# arduino_hc.net
KiCad netlist of a schematic drawn in EAGLE
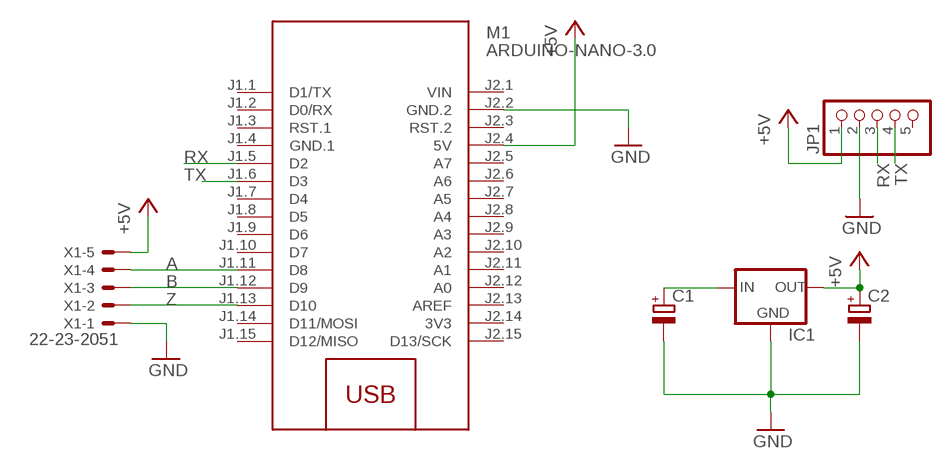
[diagram p0: schematic, sheet 1]

(export (version "E")
  (design (tool "Eeschema 10.0.6"))
  (components
    (comp (ref "C1")
      (value "CPOL-EUE2,5-6E")
      (footprint "eagle-import:E2,5-6E")
      (libsource (lib "eagle-import") (part "CPOL-EUE2,5-6E"))
    )
    (comp (ref "C2")
      (value "CPOL-EUE2,5-6E")
      (footprint "eagle-import:E2,5-6E")
      (libsource (lib "eagle-import") (part "CPOL-EUE2,5-6E"))
    )
    (comp (ref "IC1")
      (value "78XXS")
      (footprint "eagle-import:78XXS")
      (libsource (lib "eagle-import") (part "78XXS"))
    )
    (comp (ref "JP1")
      (value "PINHD-1X5")
      (footprint "eagle-import:1X05")
      (libsource (lib "eagle-import") (part "PINHD-1X5"))
    )
    (comp (ref "M1")
      (value "ARDUINO-NANO-3.0")
      (footprint "eagle-import:ARDUINO-NANO-3.0")
      (libsource (lib "eagle-import") (part "ARDUINO-NANO-3.0"))
    )
    (comp (ref "X1")
      (value "22-23-2051")
      (footprint "eagle-import:22-23-2051")
      (fields (field (name "MF") "MOLEX"))
      (libsource (lib "eagle-import") (part "22-23-2051"))
    )
  )
  (nets
    (net (code "1") (name "+5V") (class "Default")
      (node (ref "C2") (pin "+") (pinfunction "+_+") (pintype "passive"))
      (node (ref "IC1") (pin "OUT") (pinfunction "OUT_OUT") (pintype "passive"))
      (node (ref "JP1") (pin "1") (pinfunction "1_1") (pintype "passive"))
      (node (ref "M1") (pin "J2.4") (pinfunction "5V_J2.4") (pintype "power_in"))
      (node (ref "X1") (pin "5") (pinfunction "S_5") (pintype "passive"))
    )
    (net (code "2") (name "/3V3") (class "Default")
      (node (ref "M1") (pin "J2.14") (pinfunction "3V3_J2.14") (pintype "power_in"))
    )
    (net (code "3") (name "/A") (class "Default")
      (node (ref "M1") (pin "J1.11") (pinfunction "D8_J1.11") (pintype "bidirectional"))
      (node (ref "X1") (pin "4") (pinfunction "S_4") (pintype "passive"))
    )
    (net (code "4") (name "/B") (class "Default")
      (node (ref "M1") (pin "J1.12") (pinfunction "D9_J1.12") (pintype "bidirectional"))
      (node (ref "X1") (pin "3") (pinfunction "S_3") (pintype "passive"))
    )
    (net (code "5") (name "/GND.1") (class "Default")
      (node (ref "M1") (pin "J1.4") (pinfunction "GND.1_J1.4") (pintype "power_in"))
    )
    (net (code "6") (name "/RX") (class "Default")
      (node (ref "JP1") (pin "3") (pinfunction "3_3") (pintype "passive"))
      (node (ref "M1") (pin "J1.5") (pinfunction "D2_J1.5") (pintype "bidirectional"))
    )
    (net (code "7") (name "/TX") (class "Default")
      (node (ref "JP1") (pin "4") (pinfunction "4_4") (pintype "passive"))
      (node (ref "M1") (pin "J1.6") (pinfunction "D3_J1.6") (pintype "bidirectional"))
    )
    (net (code "8") (name "/VIN") (class "Default")
      (node (ref "M1") (pin "J2.1") (pinfunction "VIN_J2.1") (pintype "power_in"))
    )
    (net (code "9") (name "/Z") (class "Default")
      (node (ref "M1") (pin "J1.13") (pinfunction "D10_J1.13") (pintype "bidirectional"))
      (node (ref "X1") (pin "2") (pinfunction "S_2") (pintype "passive"))
    )
    (net (code "10") (name "GND") (class "Default")
      (node (ref "C1") (pin "-") (pinfunction "-_-") (pintype "passive"))
      (node (ref "C2") (pin "-") (pinfunction "-_-") (pintype "passive"))
      (node (ref "IC1") (pin "GND") (pinfunction "GND_GND") (pintype "input"))
      (node (ref "JP1") (pin "2") (pinfunction "2_2") (pintype "passive"))
      (node (ref "M1") (pin "J2.2") (pinfunction "GND.2_J2.2") (pintype "power_in"))
      (node (ref "X1") (pin "1") (pinfunction "S_1") (pintype "passive"))
    )
    (net (code "11") (name "Net-(C1-Pad+)") (class "Default")
      (node (ref "C1") (pin "+") (pinfunction "+_+") (pintype "passive"))
      (node (ref "IC1") (pin "IN") (pinfunction "IN_IN") (pintype "input"))
    )
    (net (code "12") (name "unconnected-(JP1-Pad5)") (class "Default")
      (node (ref "JP1") (pin "5") (pinfunction "5_5") (pintype "passive"))
    )
    (net (code "13") (name "unconnected-(M1-A0-PadJ2.12)") (class "Default")
      (node (ref "M1") (pin "J2.12") (pinfunction "A0_J2.12") (pintype "bidirectional"))
    )
    (net (code "14") (name "unconnected-(M1-A1-PadJ2.11)") (class "Default")
      (node (ref "M1") (pin "J2.11") (pinfunction "A1_J2.11") (pintype "bidirectional"))
    )
    (net (code "15") (name "unconnected-(M1-A2-PadJ2.10)") (class "Default")
      (node (ref "M1") (pin "J2.10") (pinfunction "A2_J2.10") (pintype "bidirectional"))
    )
    (net (code "16") (name "unconnected-(M1-A3-PadJ2.9)") (class "Default")
      (node (ref "M1") (pin "J2.9") (pinfunction "A3_J2.9") (pintype "bidirectional"))
    )
    (net (code "17") (name "unconnected-(M1-A4-PadJ2.8)") (class "Default")
      (node (ref "M1") (pin "J2.8") (pinfunction "A4_J2.8") (pintype "bidirectional"))
    )
    (net (code "18") (name "unconnected-(M1-A5-PadJ2.7)") (class "Default")
      (node (ref "M1") (pin "J2.7") (pinfunction "A5_J2.7") (pintype "bidirectional"))
    )
    (net (code "19") (name "unconnected-(M1-A6-PadJ2.6)") (class "Default")
      (node (ref "M1") (pin "J2.6") (pinfunction "A6_J2.6") (pintype "bidirectional"))
    )
    (net (code "20") (name "unconnected-(M1-A7-PadJ2.5)") (class "Default")
      (node (ref "M1") (pin "J2.5") (pinfunction "A7_J2.5") (pintype "bidirectional"))
    )
    (net (code "21") (name "unconnected-(M1-AREF-PadJ2.13)") (class "Default")
      (node (ref "M1") (pin "J2.13") (pinfunction "AREF_J2.13") (pintype "bidirectional"))
    )
    (net (code "22") (name "unconnected-(M1-D0{slash}RX-PadJ1.2)") (class "Default")
      (node (ref "M1") (pin "J1.2") (pinfunction "D0/RX_J1.2") (pintype "bidirectional"))
    )
    (net (code "23") (name "unconnected-(M1-D1{slash}TX-PadJ1.1)") (class "Default")
      (node (ref "M1") (pin "J1.1") (pinfunction "D1/TX_J1.1") (pintype "bidirectional"))
    )
    (net (code "24") (name "unconnected-(M1-D4-PadJ1.7)") (class "Default")
      (node (ref "M1") (pin "J1.7") (pinfunction "D4_J1.7") (pintype "bidirectional"))
    )
    (net (code "25") (name "unconnected-(M1-D5-PadJ1.8)") (class "Default")
      (node (ref "M1") (pin "J1.8") (pinfunction "D5_J1.8") (pintype "bidirectional"))
    )
    (net (code "26") (name "unconnected-(M1-D6-PadJ1.9)") (class "Default")
      (node (ref "M1") (pin "J1.9") (pinfunction "D6_J1.9") (pintype "bidirectional"))
    )
    (net (code "27") (name "unconnected-(M1-D7-PadJ1.10)") (class "Default")
      (node (ref "M1") (pin "J1.10") (pinfunction "D7_J1.10") (pintype "bidirectional"))
    )
    (net (code "28") (name "unconnected-(M1-D11{slash}MOSI-PadJ1.14)") (class "Default")
      (node (ref "M1") (pin "J1.14") (pinfunction "D11/MOSI_J1.14") (pintype "bidirectional"))
    )
    (net (code "29") (name "unconnected-(M1-D12{slash}MISO-PadJ1.15)") (class "Default")
      (node (ref "M1") (pin "J1.15") (pinfunction "D12/MISO_J1.15") (pintype "bidirectional"))
    )
    (net (code "30") (name "unconnected-(M1-D13{slash}SCK-PadJ2.15)") (class "Default")
      (node (ref "M1") (pin "J2.15") (pinfunction "D13/SCK_J2.15") (pintype "bidirectional"))
    )
    (net (code "31") (name "unconnected-(M1-RST.1-PadJ1.3)") (class "Default")
      (node (ref "M1") (pin "J1.3") (pinfunction "RST.1_J1.3") (pintype "bidirectional"))
    )
    (net (code "32") (name "unconnected-(M1-RST.2-PadJ2.3)") (class "Default")
      (node (ref "M1") (pin "J2.3") (pinfunction "RST.2_J2.3") (pintype "bidirectional"))
    )
  )
)
